# QuadPortIEC_v2.net
KiCad netlist of a schematic drawn in EAGLE
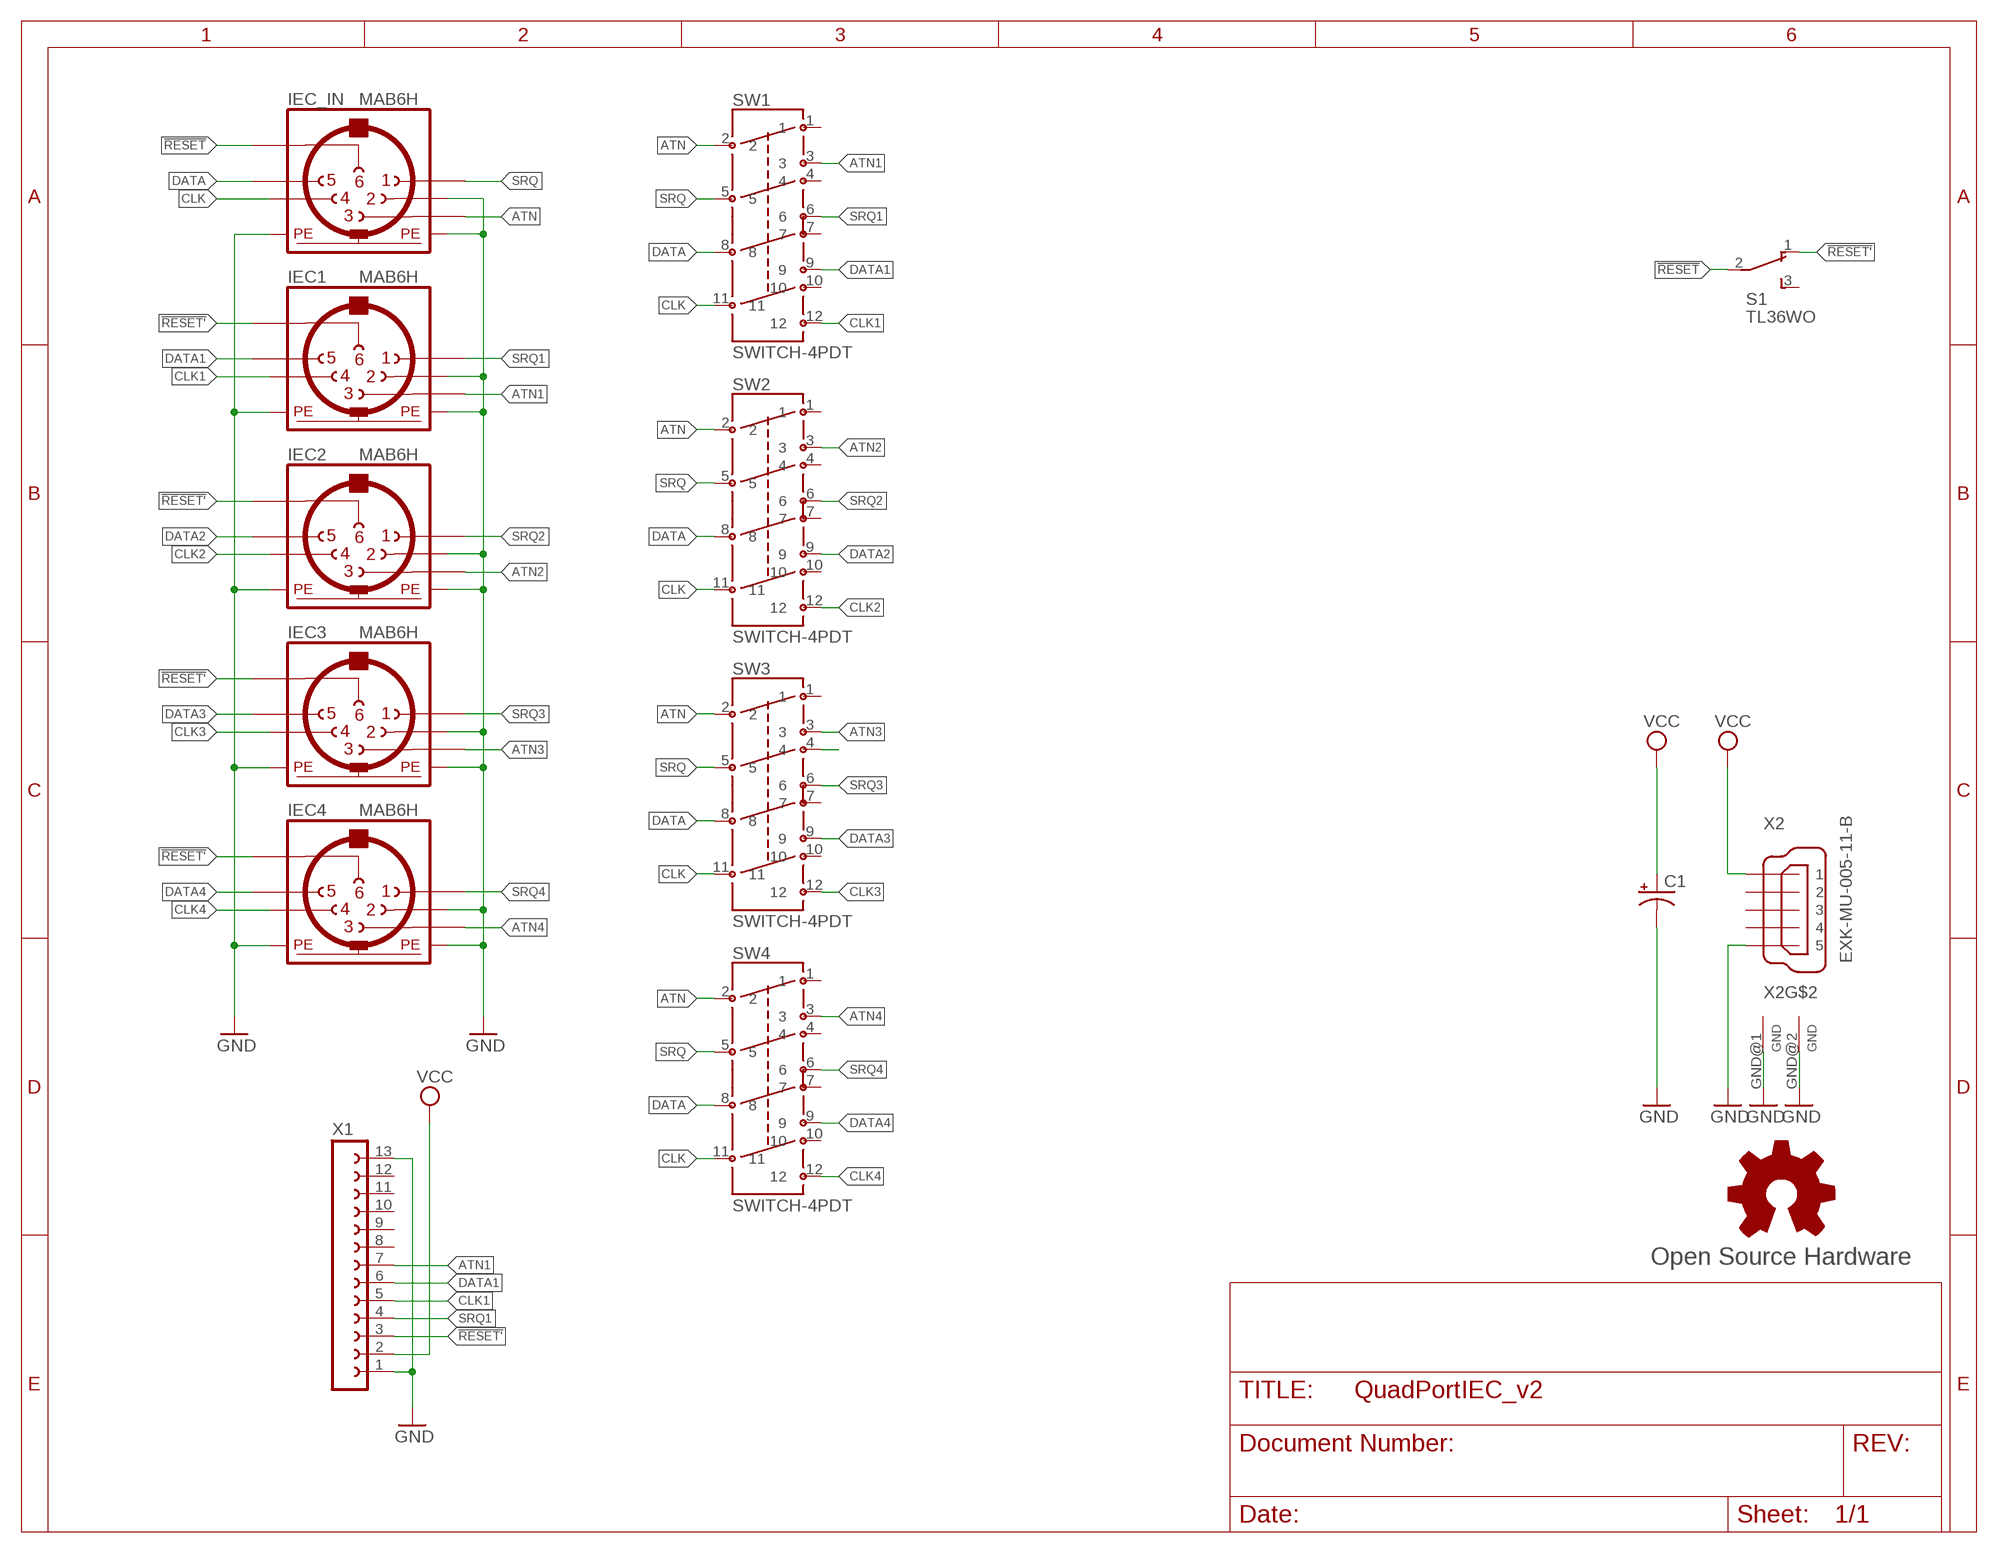
[diagram p0: schematic, sheet 1]

(export (version "E")
  (design (tool "Eeschema 10.0.6"))
  (components
    (comp (ref "C1")
      (value "CPOL-USE5-8.5")
      (footprint "eagle-import:E5-8,5")
      (libsource (lib "eagle-import") (part "CPOL-USE5-8.5"))
    )
    (comp (ref "GOLD_ORB_SM1")
      (value "Open Source Hardware")
      (footprint "eagle-import:OSHW_8MM")
      (libsource (lib "eagle-import") (part "OSHWLOGOLOGO8MM"))
    )
    (comp (ref "IEC1")
      (value "MAB6H")
      (footprint "eagle-import:MAB6H")
      (libsource (lib "eagle-import") (part "MAB6H"))
    )
    (comp (ref "IEC2")
      (value "MAB6H")
      (footprint "eagle-import:MAB6H")
      (libsource (lib "eagle-import") (part "MAB6H"))
    )
    (comp (ref "IEC3")
      (value "MAB6H")
      (footprint "eagle-import:MAB6H")
      (libsource (lib "eagle-import") (part "MAB6H"))
    )
    (comp (ref "IEC4")
      (value "MAB6H")
      (footprint "eagle-import:MAB6H")
      (libsource (lib "eagle-import") (part "MAB6H"))
    )
    (comp (ref "IEC_IN")
      (value "MAB6H")
      (footprint "eagle-import:MAB6H")
      (libsource (lib "eagle-import") (part "MAB6H"))
    )
    (comp (ref "S1")
      (value "TL36WO")
      (footprint "eagle-import:TL3XWO")
      (libsource (lib "eagle-import") (part "TL36WO"))
    )
    (comp (ref "SW1")
      (value "SWITCH-4PDT")
      (footprint "eagle-import:SWITCH-4PDT-ALPS")
      (libsource (lib "eagle-import") (part "SWITCH-4PDT"))
    )
    (comp (ref "SW2")
      (value "SWITCH-4PDT")
      (footprint "eagle-import:SWITCH-4PDT-ALPS")
      (libsource (lib "eagle-import") (part "SWITCH-4PDT"))
    )
    (comp (ref "SW3")
      (value "SWITCH-4PDT")
      (footprint "eagle-import:SWITCH-4PDT-ALPS")
      (libsource (lib "eagle-import") (part "SWITCH-4PDT"))
    )
    (comp (ref "SW4")
      (value "SWITCH-4PDT")
      (footprint "eagle-import:SWITCH-4PDT-ALPS")
      (libsource (lib "eagle-import") (part "SWITCH-4PDT"))
    )
    (comp (ref "X1")
      (value "FE13W")
      (footprint "eagle-import:FE13W")
      (libsource (lib "eagle-import") (part "FE13W"))
    )
    (comp (ref "X2")
      (value "EXK-MU-005-11-B")
      (footprint "eagle-import:MINI-USB")
      (libsource (lib "eagle-import") (part "EXK-MU-005-11-B"))
    )
  )
  (nets
    (net (code "1") (name "/~{RESET'}") (class "Default")
      (node (ref "IEC1") (pin "6") (pinfunction "6_6") (pintype "passive"))
      (node (ref "IEC2") (pin "6") (pinfunction "6_6") (pintype "passive"))
      (node (ref "IEC3") (pin "6") (pinfunction "6_6") (pintype "passive"))
      (node (ref "IEC4") (pin "6") (pinfunction "6_6") (pintype "passive"))
      (node (ref "S1") (pin "1") (pinfunction "O_1") (pintype "passive"))
      (node (ref "X1") (pin "3") (pinfunction "3_3") (pintype "passive"))
    )
    (net (code "2") (name "/~{RESET}") (class "Default")
      (node (ref "IEC_IN") (pin "6") (pinfunction "6_6") (pintype "passive"))
      (node (ref "S1") (pin "2") (pinfunction "P_2") (pintype "passive"))
    )
    (net (code "3") (name "ATN") (class "Default")
      (node (ref "IEC_IN") (pin "3") (pinfunction "3_3") (pintype "passive"))
      (node (ref "SW1") (pin "2") (pinfunction "2_2") (pintype "bidirectional"))
      (node (ref "SW2") (pin "2") (pinfunction "2_2") (pintype "bidirectional"))
      (node (ref "SW3") (pin "2") (pinfunction "2_2") (pintype "bidirectional"))
      (node (ref "SW4") (pin "2") (pinfunction "2_2") (pintype "bidirectional"))
    )
    (net (code "4") (name "ATN1") (class "Default")
      (node (ref "IEC1") (pin "3") (pinfunction "3_3") (pintype "passive"))
      (node (ref "SW1") (pin "3") (pinfunction "3_3") (pintype "bidirectional"))
      (node (ref "X1") (pin "7") (pinfunction "7_7") (pintype "passive"))
    )
    (net (code "5") (name "ATN2") (class "Default")
      (node (ref "IEC2") (pin "3") (pinfunction "3_3") (pintype "passive"))
      (node (ref "SW2") (pin "3") (pinfunction "3_3") (pintype "bidirectional"))
    )
    (net (code "6") (name "ATN3") (class "Default")
      (node (ref "IEC3") (pin "3") (pinfunction "3_3") (pintype "passive"))
      (node (ref "SW3") (pin "3") (pinfunction "3_3") (pintype "bidirectional"))
    )
    (net (code "7") (name "ATN4") (class "Default")
      (node (ref "IEC4") (pin "3") (pinfunction "3_3") (pintype "passive"))
      (node (ref "SW4") (pin "3") (pinfunction "3_3") (pintype "bidirectional"))
    )
    (net (code "8") (name "CLK") (class "Default")
      (node (ref "IEC_IN") (pin "4") (pinfunction "4_4") (pintype "passive"))
      (node (ref "SW1") (pin "11") (pinfunction "11_11") (pintype "bidirectional"))
      (node (ref "SW2") (pin "11") (pinfunction "11_11") (pintype "bidirectional"))
      (node (ref "SW3") (pin "11") (pinfunction "11_11") (pintype "bidirectional"))
      (node (ref "SW4") (pin "11") (pinfunction "11_11") (pintype "bidirectional"))
    )
    (net (code "9") (name "CLK1") (class "Default")
      (node (ref "IEC1") (pin "4") (pinfunction "4_4") (pintype "passive"))
      (node (ref "SW1") (pin "12") (pinfunction "12_12") (pintype "bidirectional"))
      (node (ref "X1") (pin "5") (pinfunction "5_5") (pintype "passive"))
    )
    (net (code "10") (name "CLK2") (class "Default")
      (node (ref "IEC2") (pin "4") (pinfunction "4_4") (pintype "passive"))
      (node (ref "SW2") (pin "12") (pinfunction "12_12") (pintype "bidirectional"))
    )
    (net (code "11") (name "CLK3") (class "Default")
      (node (ref "IEC3") (pin "4") (pinfunction "4_4") (pintype "passive"))
      (node (ref "SW3") (pin "12") (pinfunction "12_12") (pintype "bidirectional"))
    )
    (net (code "12") (name "CLK4") (class "Default")
      (node (ref "IEC4") (pin "4") (pinfunction "4_4") (pintype "passive"))
      (node (ref "SW4") (pin "12") (pinfunction "12_12") (pintype "bidirectional"))
    )
    (net (code "13") (name "DATA") (class "Default")
      (node (ref "IEC_IN") (pin "5") (pinfunction "5_5") (pintype "passive"))
      (node (ref "SW1") (pin "8") (pinfunction "8_8") (pintype "bidirectional"))
      (node (ref "SW2") (pin "8") (pinfunction "8_8") (pintype "bidirectional"))
      (node (ref "SW3") (pin "8") (pinfunction "8_8") (pintype "bidirectional"))
      (node (ref "SW4") (pin "8") (pinfunction "8_8") (pintype "bidirectional"))
    )
    (net (code "14") (name "DATA1") (class "Default")
      (node (ref "IEC1") (pin "5") (pinfunction "5_5") (pintype "passive"))
      (node (ref "SW1") (pin "9") (pinfunction "9_9") (pintype "bidirectional"))
      (node (ref "X1") (pin "6") (pinfunction "6_6") (pintype "passive"))
    )
    (net (code "15") (name "DATA2") (class "Default")
      (node (ref "IEC2") (pin "5") (pinfunction "5_5") (pintype "passive"))
      (node (ref "SW2") (pin "9") (pinfunction "9_9") (pintype "bidirectional"))
    )
    (net (code "16") (name "DATA3") (class "Default")
      (node (ref "IEC3") (pin "5") (pinfunction "5_5") (pintype "passive"))
      (node (ref "SW3") (pin "9") (pinfunction "9_9") (pintype "bidirectional"))
    )
    (net (code "17") (name "DATA4") (class "Default")
      (node (ref "IEC4") (pin "5") (pinfunction "5_5") (pintype "passive"))
      (node (ref "SW4") (pin "9") (pinfunction "9_9") (pintype "bidirectional"))
    )
    (net (code "18") (name "GND") (class "Default")
      (node (ref "C1") (pin "-") (pinfunction "-_-") (pintype "passive"))
      (node (ref "IEC1") (pin "2") (pinfunction "2_2") (pintype "passive"))
      (node (ref "IEC1") (pin "PE") (pinfunction "PE_PE") (pintype "power_in"))
      (node (ref "IEC1") (pin "PE@") (pinfunction "PE_PE@") (pintype "power_in"))
      (node (ref "IEC2") (pin "2") (pinfunction "2_2") (pintype "passive"))
      (node (ref "IEC2") (pin "PE") (pinfunction "PE_PE") (pintype "power_in"))
      (node (ref "IEC2") (pin "PE@") (pinfunction "PE_PE@") (pintype "power_in"))
      (node (ref "IEC3") (pin "2") (pinfunction "2_2") (pintype "passive"))
      (node (ref "IEC3") (pin "PE") (pinfunction "PE_PE") (pintype "power_in"))
      (node (ref "IEC3") (pin "PE@") (pinfunction "PE_PE@") (pintype "power_in"))
      (node (ref "IEC4") (pin "2") (pinfunction "2_2") (pintype "passive"))
      (node (ref "IEC4") (pin "PE") (pinfunction "PE_PE") (pintype "power_in"))
      (node (ref "IEC4") (pin "PE@") (pinfunction "PE_PE@") (pintype "power_in"))
      (node (ref "IEC_IN") (pin "2") (pinfunction "2_2") (pintype "passive"))
      (node (ref "IEC_IN") (pin "PE") (pinfunction "PE_PE") (pintype "power_in"))
      (node (ref "IEC_IN") (pin "PE@") (pinfunction "PE_PE@") (pintype "power_in"))
      (node (ref "X1") (pin "1") (pinfunction "1_1") (pintype "passive"))
      (node (ref "X1") (pin "13") (pinfunction "13_13") (pintype "passive"))
      (node (ref "X2") (pin "GND") (pinfunction "5_GND") (pintype "input"))
      (node (ref "X2") (pin "GND@1") (pinfunction "GND_GND@1") (pintype "power_in"))
      (node (ref "X2") (pin "GND@2") (pinfunction "GND_GND@2") (pintype "power_in"))
    )
    (net (code "19") (name "SRQ") (class "Default")
      (node (ref "IEC_IN") (pin "1") (pinfunction "1_1") (pintype "passive"))
      (node (ref "SW1") (pin "5") (pinfunction "5_5") (pintype "bidirectional"))
      (node (ref "SW2") (pin "5") (pinfunction "5_5") (pintype "bidirectional"))
      (node (ref "SW3") (pin "5") (pinfunction "5_5") (pintype "bidirectional"))
      (node (ref "SW4") (pin "5") (pinfunction "5_5") (pintype "bidirectional"))
    )
    (net (code "20") (name "SRQ1") (class "Default")
      (node (ref "IEC1") (pin "1") (pinfunction "1_1") (pintype "passive"))
      (node (ref "SW1") (pin "6") (pinfunction "6_6") (pintype "bidirectional"))
      (node (ref "X1") (pin "4") (pinfunction "4_4") (pintype "passive"))
    )
    (net (code "21") (name "SRQ2") (class "Default")
      (node (ref "IEC2") (pin "1") (pinfunction "1_1") (pintype "passive"))
      (node (ref "SW2") (pin "6") (pinfunction "6_6") (pintype "bidirectional"))
    )
    (net (code "22") (name "SRQ3") (class "Default")
      (node (ref "IEC3") (pin "1") (pinfunction "1_1") (pintype "passive"))
      (node (ref "SW3") (pin "6") (pinfunction "6_6") (pintype "bidirectional"))
    )
    (net (code "23") (name "SRQ4") (class "Default")
      (node (ref "IEC4") (pin "1") (pinfunction "1_1") (pintype "passive"))
      (node (ref "SW4") (pin "6") (pinfunction "6_6") (pintype "bidirectional"))
    )
    (net (code "24") (name "VCC") (class "Default")
      (node (ref "C1") (pin "+") (pinfunction "+_+") (pintype "passive"))
      (node (ref "X1") (pin "2") (pinfunction "2_2") (pintype "passive"))
      (node (ref "X2") (pin "VBUS") (pinfunction "1_VBUS") (pintype "input"))
    )
    (net (code "25") (name "unconnected-(S1-S-Pad3)") (class "Default")
      (node (ref "S1") (pin "3") (pinfunction "S_3") (pintype "passive"))
    )
    (net (code "26") (name "unconnected-(SW1-Pad1)") (class "Default")
      (node (ref "SW1") (pin "1") (pinfunction "1_1") (pintype "bidirectional"))
    )
    (net (code "27") (name "unconnected-(SW1-Pad4)") (class "Default")
      (node (ref "SW1") (pin "4") (pinfunction "4_4") (pintype "bidirectional"))
    )
    (net (code "28") (name "unconnected-(SW1-Pad7)") (class "Default")
      (node (ref "SW1") (pin "7") (pinfunction "7_7") (pintype "bidirectional"))
    )
    (net (code "29") (name "unconnected-(SW1-Pad10)") (class "Default")
      (node (ref "SW1") (pin "10") (pinfunction "10_10") (pintype "bidirectional"))
    )
    (net (code "30") (name "unconnected-(SW2-Pad1)") (class "Default")
      (node (ref "SW2") (pin "1") (pinfunction "1_1") (pintype "bidirectional"))
    )
    (net (code "31") (name "unconnected-(SW2-Pad4)") (class "Default")
      (node (ref "SW2") (pin "4") (pinfunction "4_4") (pintype "bidirectional"))
    )
    (net (code "32") (name "unconnected-(SW2-Pad7)") (class "Default")
      (node (ref "SW2") (pin "7") (pinfunction "7_7") (pintype "bidirectional"))
    )
    (net (code "33") (name "unconnected-(SW2-Pad10)") (class "Default")
      (node (ref "SW2") (pin "10") (pinfunction "10_10") (pintype "bidirectional"))
    )
    (net (code "34") (name "unconnected-(SW3-Pad1)") (class "Default")
      (node (ref "SW3") (pin "1") (pinfunction "1_1") (pintype "bidirectional"))
    )
    (net (code "35") (name "unconnected-(SW3-Pad4)") (class "Default")
      (node (ref "SW3") (pin "4") (pinfunction "4_4") (pintype "bidirectional"))
    )
    (net (code "36") (name "unconnected-(SW3-Pad7)") (class "Default")
      (node (ref "SW3") (pin "7") (pinfunction "7_7") (pintype "bidirectional"))
    )
    (net (code "37") (name "unconnected-(SW3-Pad10)") (class "Default")
      (node (ref "SW3") (pin "10") (pinfunction "10_10") (pintype "bidirectional"))
    )
    (net (code "38") (name "unconnected-(SW4-Pad1)") (class "Default")
      (node (ref "SW4") (pin "1") (pinfunction "1_1") (pintype "bidirectional"))
    )
    (net (code "39") (name "unconnected-(SW4-Pad4)") (class "Default")
      (node (ref "SW4") (pin "4") (pinfunction "4_4") (pintype "bidirectional"))
    )
    (net (code "40") (name "unconnected-(SW4-Pad7)") (class "Default")
      (node (ref "SW4") (pin "7") (pinfunction "7_7") (pintype "bidirectional"))
    )
    (net (code "41") (name "unconnected-(SW4-Pad10)") (class "Default")
      (node (ref "SW4") (pin "10") (pinfunction "10_10") (pintype "bidirectional"))
    )
    (net (code "42") (name "unconnected-(X1-Pad8)") (class "Default")
      (node (ref "X1") (pin "8") (pinfunction "8_8") (pintype "passive"))
    )
    (net (code "43") (name "unconnected-(X1-Pad9)") (class "Default")
      (node (ref "X1") (pin "9") (pinfunction "9_9") (pintype "passive"))
    )
    (net (code "44") (name "unconnected-(X1-Pad10)") (class "Default")
      (node (ref "X1") (pin "10") (pinfunction "10_10") (pintype "passive"))
    )
    (net (code "45") (name "unconnected-(X1-Pad11)") (class "Default")
      (node (ref "X1") (pin "11") (pinfunction "11_11") (pintype "passive"))
    )
    (net (code "46") (name "unconnected-(X1-Pad12)") (class "Default")
      (node (ref "X1") (pin "12") (pinfunction "12_12") (pintype "passive"))
    )
    (net (code "47") (name "unconnected-(X2A-2-PadD-)") (class "Default")
      (node (ref "X2") (pin "D-") (pinfunction "2_D-") (pintype "input"))
    )
    (net (code "48") (name "unconnected-(X2A-3-PadD+)") (class "Default")
      (node (ref "X2") (pin "D+") (pinfunction "3_D+") (pintype "input"))
    )
    (net (code "49") (name "unconnected-(X2A-4-PadID)") (class "Default")
      (node (ref "X2") (pin "ID") (pinfunction "4_ID") (pintype "input"))
    )
  )
)
